# L_ftungssteuerung.net
KiCad netlist of a schematic drawn in EAGLE
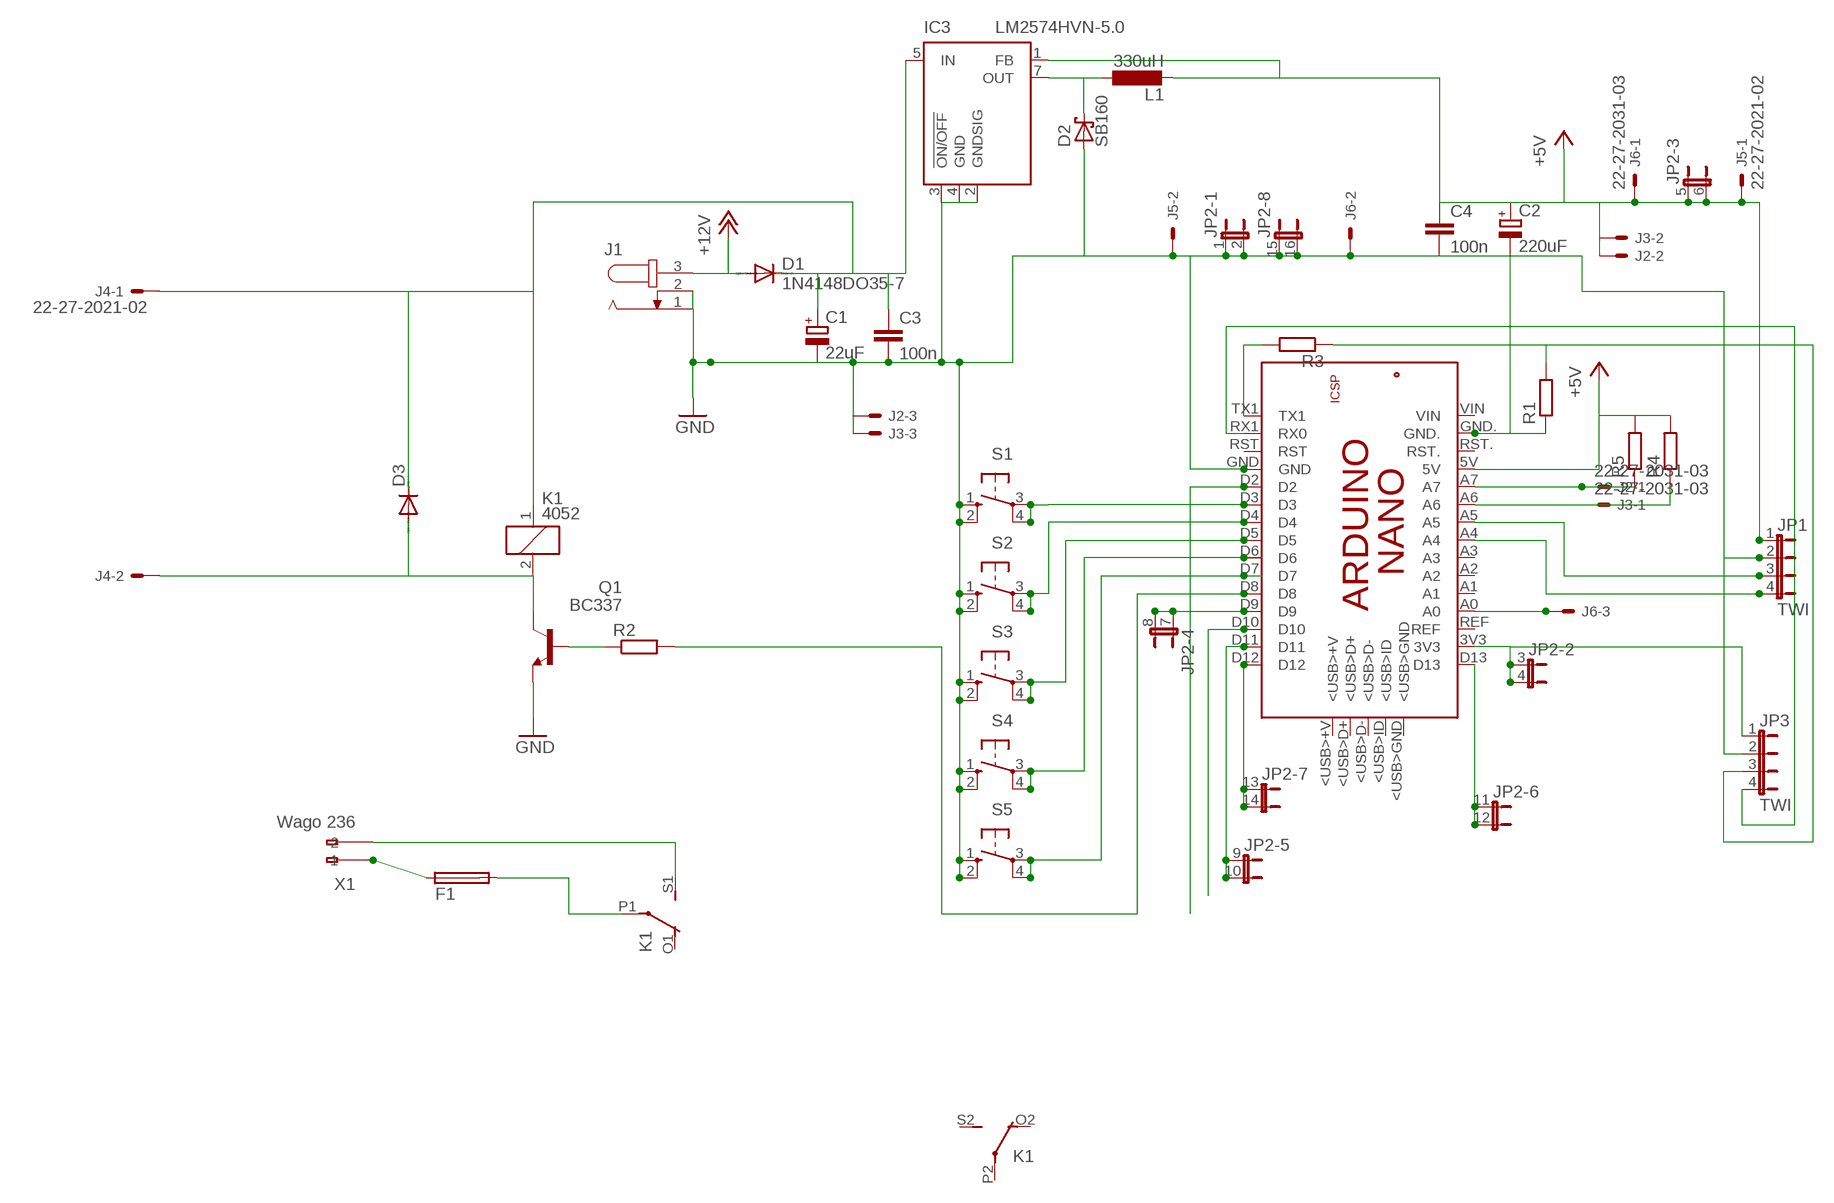
[diagram p0: schematic, sheet 1]

(export (version "E")
  (design (tool "Eeschema 10.0.6"))
  (components
    (comp (ref "C1")
      (value "22uF")
      (footprint "eagle-import:E2-5")
      (libsource (lib "eagle-import") (part "CPOL-EUE2-5"))
    )
    (comp (ref "C2")
      (value "220uF")
      (footprint "eagle-import:E5-10,5")
      (libsource (lib "eagle-import") (part "CPOL-EUE5-10.5"))
    )
    (comp (ref "C3")
      (value "100n")
      (footprint "eagle-import:C1206")
      (libsource (lib "eagle-import") (part "C-EUC1206"))
    )
    (comp (ref "C4")
      (value "100n")
      (footprint "eagle-import:C1206")
      (libsource (lib "eagle-import") (part "C-EUC1206"))
    )
    (comp (ref "D1")
      (value "1N4148DO35-7")
      (footprint "eagle-import:DO35-7")
      (libsource (lib "eagle-import") (part "1N4148DO35-7"))
    )
    (comp (ref "D2")
      (value "SB160")
      (footprint "eagle-import:DO41-7.6")
      (libsource (lib "eagle-import") (part "1N5817-B"))
    )
    (comp (ref "D3")
      (value "DIODE-DO41-7.6")
      (footprint "eagle-import:DO41-7.6")
      (libsource (lib "eagle-import") (part "DIODE-DO41-7.6"))
    )
    (comp (ref "F1")
      (value "SH22,5")
      (footprint "eagle-import:SH22,5")
      (fields (field (name "MF") "SCHURTER") (field (name "MPN") "0031.8201"))
      (libsource (lib "eagle-import") (part "SH22,5"))
    )
    (comp (ref "IC3")
      (value "LM2574HVN-5.0")
      (footprint "eagle-import:DIL08")
      (libsource (lib "eagle-import") (part "LM2574?-HVN5.0"))
    )
    (comp (ref "J1")
      (value "JACK-PLUG0")
      (footprint "eagle-import:SPC4077")
      (libsource (lib "eagle-import") (part "JACK-PLUG0"))
    )
    (comp (ref "J2")
      (value "22-27-2031-03")
      (footprint "eagle-import:6410-03")
      (libsource (lib "eagle-import") (part "22-?-0327-2031"))
    )
    (comp (ref "J3")
      (value "22-27-2031-03")
      (footprint "eagle-import:6410-03")
      (libsource (lib "eagle-import") (part "22-?-0327-2031"))
    )
    (comp (ref "J4")
      (value "22-27-2021-02")
      (footprint "eagle-import:6410-02")
      (libsource (lib "eagle-import") (part "22-?-0227-2021"))
    )
    (comp (ref "J5")
      (value "22-27-2021-02")
      (footprint "eagle-import:6410-02")
      (libsource (lib "eagle-import") (part "22-?-0227-2021"))
    )
    (comp (ref "J6")
      (value "22-27-2031-03")
      (footprint "eagle-import:6410-03")
      (libsource (lib "eagle-import") (part "22-?-0327-2031"))
    )
    (comp (ref "JP1")
      (value "TWI")
      (footprint "eagle-import:JP4")
      (libsource (lib "eagle-import") (part "JP4E"))
    )
    (comp (ref "JP2")
      (value "JP8QE")
      (footprint "eagle-import:JP8Q")
      (libsource (lib "eagle-import") (part "JP8QE"))
    )
    (comp (ref "JP3")
      (value "TWI")
      (footprint "eagle-import:JP4")
      (libsource (lib "eagle-import") (part "JP4E"))
    )
    (comp (ref "K1")
      (value "4052")
      (footprint "eagle-import:F4052")
      (libsource (lib "eagle-import") (part "4052"))
    )
    (comp (ref "L1")
      (value "330uH")
      (footprint "eagle-import:PIS47XX")
      (libsource (lib "eagle-import") (part "L-EUPIS47XX"))
    )
    (comp (ref "PCB1")
      (value "ARDUINO_NANO")
      (footprint "eagle-import:ARDUINO_NANO")
      (libsource (lib "eagle-import") (part "ARDUINO_NANO"))
    )
    (comp (ref "Q1")
      (value "BC337")
      (footprint "eagle-import:TO92")
      (libsource (lib "eagle-import") (part "BC337"))
    )
    (comp (ref "R1")
      (value "R-EU_R1206")
      (footprint "eagle-import:R1206")
      (libsource (lib "eagle-import") (part "R-EU_R1206"))
    )
    (comp (ref "R2")
      (value "R-EU_R1206")
      (footprint "eagle-import:R1206")
      (libsource (lib "eagle-import") (part "R-EU_R1206"))
    )
    (comp (ref "R3")
      (value "R-EU_R1206")
      (footprint "eagle-import:R1206")
      (libsource (lib "eagle-import") (part "R-EU_R1206"))
    )
    (comp (ref "R4")
      (value "R-EU_R1206")
      (footprint "eagle-import:R1206")
      (libsource (lib "eagle-import") (part "R-EU_R1206"))
    )
    (comp (ref "R5")
      (value "R-EU_R1206")
      (footprint "eagle-import:R1206")
      (libsource (lib "eagle-import") (part "R-EU_R1206"))
    )
    (comp (ref "S1")
      (value "10-XX")
      (footprint "eagle-import:B3F-10XX")
      (fields (field (name "MPN") "B3F-1000"))
      (libsource (lib "eagle-import") (part "10-XX"))
    )
    (comp (ref "S2")
      (value "10-XX")
      (footprint "eagle-import:B3F-10XX")
      (fields (field (name "MPN") "B3F-1000"))
      (libsource (lib "eagle-import") (part "10-XX"))
    )
    (comp (ref "S3")
      (value "10-XX")
      (footprint "eagle-import:B3F-10XX")
      (fields (field (name "MPN") "B3F-1000"))
      (libsource (lib "eagle-import") (part "10-XX"))
    )
    (comp (ref "S4")
      (value "10-XX")
      (footprint "eagle-import:B3F-10XX")
      (fields (field (name "MPN") "B3F-1000"))
      (libsource (lib "eagle-import") (part "10-XX"))
    )
    (comp (ref "S5")
      (value "10-XX")
      (footprint "eagle-import:B3F-10XX")
      (fields (field (name "MPN") "B3F-1000"))
      (libsource (lib "eagle-import") (part "10-XX"))
    )
    (comp (ref "X1")
      (value "Wago 236")
      (footprint "eagle-import:255-402-508")
      (libsource (lib "eagle-import") (part "255-402-508"))
    )
  )
  (nets
    (net (code "1") (name "+5V") (class "Default")
      (node (ref "C2") (pin "+") (pinfunction "+_+") (pintype "passive"))
      (node (ref "C4") (pin "1") (pinfunction "1_1") (pintype "passive"))
      (node (ref "IC3") (pin "1") (pinfunction "FB_1") (pintype "input"))
      (node (ref "J2") (pin "2") (pinfunction "S_2") (pintype "passive"))
      (node (ref "J3") (pin "2") (pinfunction "S_2") (pintype "passive"))
      (node (ref "J5") (pin "1") (pinfunction "S_1") (pintype "passive"))
      (node (ref "J6") (pin "1") (pinfunction "S_1") (pintype "passive"))
      (node (ref "JP1") (pin "1") (pinfunction "1_1") (pintype "passive"))
      (node (ref "JP2") (pin "5") (pinfunction "1_5") (pintype "passive"))
      (node (ref "JP2") (pin "6") (pinfunction "2_6") (pintype "passive"))
      (node (ref "L1") (pin "1") (pinfunction "2_1") (pintype "passive"))
      (node (ref "PCB1") (pin "5V") (pinfunction "5V_5V") (pintype "bidirectional"))
      (node (ref "R4") (pin "2") (pinfunction "2_2") (pintype "passive"))
      (node (ref "R5") (pin "2") (pinfunction "2_2") (pintype "passive"))
    )
    (net (code "2") (name "+12V") (class "Default")
      (node (ref "D1") (pin "A") (pinfunction "A_A") (pintype "passive"))
      (node (ref "J1") (pin "3") (pinfunction "3_3") (pintype "passive"))
    )
    (net (code "3") (name "GND") (class "Default")
      (node (ref "C1") (pin "-") (pinfunction "-_-") (pintype "passive"))
      (node (ref "C2") (pin "-") (pinfunction "-_-") (pintype "passive"))
      (node (ref "C3") (pin "2") (pinfunction "2_2") (pintype "passive"))
      (node (ref "C4") (pin "2") (pinfunction "2_2") (pintype "passive"))
      (node (ref "D2") (pin "A") (pinfunction "A_A") (pintype "passive"))
      (node (ref "IC3") (pin "2") (pinfunction "GNDSIG_2") (pintype "input"))
      (node (ref "IC3") (pin "3") (pinfunction "~{ON/OFF}_3") (pintype "input"))
      (node (ref "IC3") (pin "4") (pinfunction "GND_4") (pintype "power_in"))
      (node (ref "J1") (pin "1") (pinfunction "1_1") (pintype "passive"))
      (node (ref "J1") (pin "2") (pinfunction "2_2") (pintype "passive"))
      (node (ref "J2") (pin "3") (pinfunction "S_3") (pintype "passive"))
      (node (ref "J3") (pin "3") (pinfunction "S_3") (pintype "passive"))
      (node (ref "J5") (pin "2") (pinfunction "S_2") (pintype "passive"))
      (node (ref "J6") (pin "2") (pinfunction "S_2") (pintype "passive"))
      (node (ref "JP1") (pin "2") (pinfunction "2_2") (pintype "passive"))
      (node (ref "JP2") (pin "1") (pinfunction "1_1") (pintype "passive"))
      (node (ref "JP2") (pin "15") (pinfunction "1_15") (pintype "passive"))
      (node (ref "JP2") (pin "16") (pinfunction "2_16") (pintype "passive"))
      (node (ref "JP2") (pin "2") (pinfunction "2_2") (pintype "passive"))
      (node (ref "JP3") (pin "2") (pinfunction "2_2") (pintype "passive"))
      (node (ref "PCB1") (pin "GND") (pinfunction "GND_GND") (pintype "bidirectional"))
      (node (ref "PCB1") (pin "GND.") (pinfunction "GND._GND.") (pintype "bidirectional"))
      (node (ref "Q1") (pin "1") (pinfunction "E_1") (pintype "passive"))
      (node (ref "R1") (pin "1") (pinfunction "1_1") (pintype "passive"))
      (node (ref "S1") (pin "1") (pinfunction "S_1") (pintype "passive"))
      (node (ref "S1") (pin "2") (pinfunction "S1_2") (pintype "passive"))
      (node (ref "S2") (pin "1") (pinfunction "S_1") (pintype "passive"))
      (node (ref "S2") (pin "2") (pinfunction "S1_2") (pintype "passive"))
      (node (ref "S3") (pin "1") (pinfunction "S_1") (pintype "passive"))
      (node (ref "S3") (pin "2") (pinfunction "S1_2") (pintype "passive"))
      (node (ref "S4") (pin "1") (pinfunction "S_1") (pintype "passive"))
      (node (ref "S4") (pin "2") (pinfunction "S1_2") (pintype "passive"))
      (node (ref "S5") (pin "1") (pinfunction "S_1") (pintype "passive"))
      (node (ref "S5") (pin "2") (pinfunction "S1_2") (pintype "passive"))
    )
    (net (code "4") (name "Net-(IC3-IN)") (class "Default")
      (node (ref "C1") (pin "+") (pinfunction "+_+") (pintype "passive"))
      (node (ref "C3") (pin "1") (pinfunction "1_1") (pintype "passive"))
      (node (ref "D1") (pin "C") (pinfunction "C_C") (pintype "passive"))
      (node (ref "D3") (pin "C") (pinfunction "C_C") (pintype "passive"))
      (node (ref "IC3") (pin "5") (pinfunction "IN_5") (pintype "input"))
      (node (ref "J4") (pin "1") (pinfunction "S_1") (pintype "passive"))
      (node (ref "K1") (pin "1") (pinfunction "1_1") (pintype "passive"))
    )
    (net (code "5") (name "Net-(IC3-OUT)") (class "Default")
      (node (ref "D2") (pin "C") (pinfunction "C_C") (pintype "passive"))
      (node (ref "IC3") (pin "7") (pinfunction "OUT_7") (pintype "passive"))
      (node (ref "L1") (pin "2") (pinfunction "1_2") (pintype "passive"))
    )
    (net (code "6") (name "Net-(J2A-S)") (class "Default")
      (node (ref "J2") (pin "1") (pinfunction "S_1") (pintype "passive"))
      (node (ref "PCB1") (pin "A7") (pinfunction "A7_A7") (pintype "bidirectional"))
      (node (ref "R5") (pin "1") (pinfunction "1_1") (pintype "passive"))
    )
    (net (code "7") (name "Net-(J3A-S)") (class "Default")
      (node (ref "J3") (pin "1") (pinfunction "S_1") (pintype "passive"))
      (node (ref "PCB1") (pin "A6") (pinfunction "A6_A6") (pintype "bidirectional"))
      (node (ref "R4") (pin "1") (pinfunction "1_1") (pintype "passive"))
    )
    (net (code "8") (name "Net-(J4B-S)") (class "Default")
      (node (ref "D3") (pin "A") (pinfunction "A_A") (pintype "passive"))
      (node (ref "J4") (pin "2") (pinfunction "S_2") (pintype "passive"))
      (node (ref "K1") (pin "2") (pinfunction "2_2") (pintype "passive"))
      (node (ref "Q1") (pin "3") (pinfunction "C_3") (pintype "passive"))
    )
    (net (code "9") (name "Net-(J6C-S)") (class "Default")
      (node (ref "J6") (pin "3") (pinfunction "S_3") (pintype "passive"))
      (node (ref "PCB1") (pin "A0") (pinfunction "A0_A0") (pintype "bidirectional"))
    )
    (net (code "10") (name "Net-(JP1-Pad3)") (class "Default")
      (node (ref "JP1") (pin "3") (pinfunction "3_3") (pintype "passive"))
      (node (ref "PCB1") (pin "A5") (pinfunction "A5_A5") (pintype "bidirectional"))
    )
    (net (code "11") (name "Net-(JP1-Pad4)") (class "Default")
      (node (ref "JP1") (pin "4") (pinfunction "4_4") (pintype "passive"))
      (node (ref "PCB1") (pin "A4") (pinfunction "A4_A4") (pintype "bidirectional"))
    )
    (net (code "12") (name "Net-(JP2B-1)") (class "Default")
      (node (ref "JP2") (pin "3") (pinfunction "1_3") (pintype "passive"))
      (node (ref "JP2") (pin "4") (pinfunction "2_4") (pintype "passive"))
      (node (ref "JP3") (pin "1") (pinfunction "1_1") (pintype "passive"))
      (node (ref "PCB1") (pin "3V3") (pinfunction "3V3_3V3") (pintype "bidirectional"))
    )
    (net (code "13") (name "Net-(JP2D-1)") (class "Default")
      (node (ref "JP2") (pin "7") (pinfunction "1_7") (pintype "passive"))
      (node (ref "JP2") (pin "8") (pinfunction "2_8") (pintype "passive"))
      (node (ref "PCB1") (pin "D9") (pinfunction "D9_D9") (pintype "bidirectional"))
    )
    (net (code "14") (name "Net-(JP2E-1)") (class "Default")
      (node (ref "JP2") (pin "10") (pinfunction "2_10") (pintype "passive"))
      (node (ref "JP2") (pin "9") (pinfunction "1_9") (pintype "passive"))
      (node (ref "PCB1") (pin "D11") (pinfunction "D11_D11") (pintype "bidirectional"))
    )
    (net (code "15") (name "Net-(JP2F-1)") (class "Default")
      (node (ref "JP2") (pin "11") (pinfunction "1_11") (pintype "passive"))
      (node (ref "JP2") (pin "12") (pinfunction "2_12") (pintype "passive"))
      (node (ref "PCB1") (pin "D13") (pinfunction "D13_D13") (pintype "bidirectional"))
    )
    (net (code "16") (name "Net-(JP2G-1)") (class "Default")
      (node (ref "JP2") (pin "13") (pinfunction "1_13") (pintype "passive"))
      (node (ref "JP2") (pin "14") (pinfunction "2_14") (pintype "passive"))
      (node (ref "PCB1") (pin "D12") (pinfunction "D12_D12") (pintype "bidirectional"))
    )
    (net (code "17") (name "Net-(JP3-Pad3)") (class "Default")
      (node (ref "JP3") (pin "3") (pinfunction "3_3") (pintype "passive"))
      (node (ref "R1") (pin "2") (pinfunction "2_2") (pintype "passive"))
      (node (ref "R3") (pin "1") (pinfunction "1_1") (pintype "passive"))
    )
    (net (code "18") (name "Net-(K1B-P)") (class "Default")
      (node (ref "F1") (pin "2") (pinfunction "2_2") (pintype "passive"))
      (node (ref "K1") (pin "P1") (pinfunction "P_P1") (pintype "passive"))
    )
    (net (code "19") (name "Net-(K1B-S)") (class "Default")
      (node (ref "K1") (pin "S1") (pinfunction "S_S1") (pintype "passive"))
      (node (ref "X1") (pin "A2") (pinfunction "-2_A2") (pintype "passive"))
    )
    (net (code "20") (name "Net-(PCB1-PadD8)") (class "Default")
      (node (ref "PCB1") (pin "D8") (pinfunction "D8_D8") (pintype "bidirectional"))
      (node (ref "R2") (pin "2") (pinfunction "2_2") (pintype "passive"))
    )
    (net (code "21") (name "Net-(PCB1-PadTX1)") (class "Default")
      (node (ref "PCB1") (pin "TX1") (pinfunction "TX1_TX1") (pintype "bidirectional"))
      (node (ref "R3") (pin "2") (pinfunction "2_2") (pintype "passive"))
    )
    (net (code "22") (name "Net-(PCB1-RX0)") (class "Default")
      (node (ref "JP3") (pin "4") (pinfunction "4_4") (pintype "passive"))
      (node (ref "PCB1") (pin "RX1") (pinfunction "RX0_RX1") (pintype "bidirectional"))
    )
    (net (code "23") (name "Net-(Q1-B)") (class "Default")
      (node (ref "Q1") (pin "2") (pinfunction "B_2") (pintype "passive"))
      (node (ref "R2") (pin "1") (pinfunction "1_1") (pintype "passive"))
    )
    (net (code "24") (name "Net-(S1-P)") (class "Default")
      (node (ref "PCB1") (pin "D3") (pinfunction "D3_D3") (pintype "bidirectional"))
      (node (ref "S1") (pin "3") (pinfunction "P_3") (pintype "passive"))
      (node (ref "S1") (pin "4") (pinfunction "P1_4") (pintype "passive"))
    )
    (net (code "25") (name "Net-(S2-P)") (class "Default")
      (node (ref "PCB1") (pin "D4") (pinfunction "D4_D4") (pintype "bidirectional"))
      (node (ref "S2") (pin "3") (pinfunction "P_3") (pintype "passive"))
      (node (ref "S2") (pin "4") (pinfunction "P1_4") (pintype "passive"))
    )
    (net (code "26") (name "Net-(S3-P)") (class "Default")
      (node (ref "PCB1") (pin "D5") (pinfunction "D5_D5") (pintype "bidirectional"))
      (node (ref "S3") (pin "3") (pinfunction "P_3") (pintype "passive"))
      (node (ref "S3") (pin "4") (pinfunction "P1_4") (pintype "passive"))
    )
    (net (code "27") (name "Net-(S4-P)") (class "Default")
      (node (ref "PCB1") (pin "D6") (pinfunction "D6_D6") (pintype "bidirectional"))
      (node (ref "S4") (pin "3") (pinfunction "P_3") (pintype "passive"))
      (node (ref "S4") (pin "4") (pinfunction "P1_4") (pintype "passive"))
    )
    (net (code "28") (name "Net-(S5-P)") (class "Default")
      (node (ref "PCB1") (pin "D7") (pinfunction "D7_D7") (pintype "bidirectional"))
      (node (ref "S5") (pin "3") (pinfunction "P_3") (pintype "passive"))
      (node (ref "S5") (pin "4") (pinfunction "P1_4") (pintype "passive"))
    )
    (net (code "29") (name "Net-(X1--1)") (class "Default")
      (node (ref "F1") (pin "1") (pinfunction "1_1") (pintype "passive"))
      (node (ref "X1") (pin "A1") (pinfunction "-1_A1") (pintype "passive"))
    )
    (net (code "30") (name "unconnected-(K1B-O-PadO1)") (class "Default")
      (node (ref "K1") (pin "O1") (pinfunction "O_O1") (pintype "passive"))
    )
    (net (code "31") (name "unconnected-(K1C-O-PadO2)") (class "Default")
      (node (ref "K1") (pin "O2") (pinfunction "O_O2") (pintype "passive"))
    )
    (net (code "32") (name "unconnected-(K1C-P-PadP2)") (class "Default")
      (node (ref "K1") (pin "P2") (pinfunction "P_P2") (pintype "passive"))
    )
    (net (code "33") (name "unconnected-(K1C-S-PadS2)") (class "Default")
      (node (ref "K1") (pin "S2") (pinfunction "S_S2") (pintype "passive"))
    )
    (net (code "34") (name "unconnected-(PCB1-Pad5V.)") (class "Default")
      (node (ref "PCB1") (pin "5V.") (pinfunction "5V._5V.") (pintype "bidirectional"))
    )
    (net (code "35") (name "unconnected-(PCB1-Pad<USB>+V)") (class "Default")
      (node (ref "PCB1") (pin "<USB>+V") (pinfunction "<USB>+V_<USB>+V") (pintype "bidirectional"))
    )
    (net (code "36") (name "unconnected-(PCB1-Pad<USB>D+)") (class "Default")
      (node (ref "PCB1") (pin "<USB>D+") (pinfunction "<USB>D+_<USB>D+") (pintype "bidirectional"))
    )
    (net (code "37") (name "unconnected-(PCB1-Pad<USB>D-)") (class "Default")
      (node (ref "PCB1") (pin "<USB>D-") (pinfunction "<USB>D-_<USB>D-") (pintype "bidirectional"))
    )
    (net (code "38") (name "unconnected-(PCB1-Pad<USB>GND)") (class "Default")
      (node (ref "PCB1") (pin "<USB>GND") (pinfunction "<USB>GND_<USB>GND") (pintype "bidirectional"))
    )
    (net (code "39") (name "unconnected-(PCB1-Pad<USB>ID)") (class "Default")
      (node (ref "PCB1") (pin "<USB>ID") (pinfunction "<USB>ID_<USB>ID") (pintype "bidirectional"))
    )
    (net (code "40") (name "unconnected-(PCB1-PadA1)") (class "Default")
      (node (ref "PCB1") (pin "A1") (pinfunction "A1_A1") (pintype "bidirectional"))
    )
    (net (code "41") (name "unconnected-(PCB1-PadA2)") (class "Default")
      (node (ref "PCB1") (pin "A2") (pinfunction "A2_A2") (pintype "bidirectional"))
    )
    (net (code "42") (name "unconnected-(PCB1-PadA3)") (class "Default")
      (node (ref "PCB1") (pin "A3") (pinfunction "A3_A3") (pintype "bidirectional"))
    )
    (net (code "43") (name "unconnected-(PCB1-PadD2)") (class "Default")
      (node (ref "PCB1") (pin "D2") (pinfunction "D2_D2") (pintype "bidirectional"))
    )
    (net (code "44") (name "unconnected-(PCB1-PadD10)") (class "Default")
      (node (ref "PCB1") (pin "D10") (pinfunction "D10_D10") (pintype "bidirectional"))
    )
    (net (code "45") (name "unconnected-(PCB1-PadGND_)") (class "Default")
      (node (ref "PCB1") (pin "GND_") (pinfunction "GND__GND_") (pintype "bidirectional"))
    )
    (net (code "46") (name "unconnected-(PCB1-PadMISO)") (class "Default")
      (node (ref "PCB1") (pin "MISO") (pinfunction "MISO_MISO") (pintype "bidirectional"))
    )
    (net (code "47") (name "unconnected-(PCB1-PadMOSI)") (class "Default")
      (node (ref "PCB1") (pin "MOSI") (pinfunction "MOSI_MOSI") (pintype "bidirectional"))
    )
    (net (code "48") (name "unconnected-(PCB1-PadREF)") (class "Default")
      (node (ref "PCB1") (pin "REF") (pinfunction "REF_REF") (pintype "bidirectional"))
    )
    (net (code "49") (name "unconnected-(PCB1-PadRESET..)") (class "Default")
      (node (ref "PCB1") (pin "RESET..") (pinfunction "RESET.._RESET..") (pintype "bidirectional"))
    )
    (net (code "50") (name "unconnected-(PCB1-PadRST)") (class "Default")
      (node (ref "PCB1") (pin "RST") (pinfunction "RST_RST") (pintype "bidirectional"))
    )
    (net (code "51") (name "unconnected-(PCB1-PadRST.)") (class "Default")
      (node (ref "PCB1") (pin "RST.") (pinfunction "RST._RST.") (pintype "bidirectional"))
    )
    (net (code "52") (name "unconnected-(PCB1-PadSCK)") (class "Default")
      (node (ref "PCB1") (pin "SCK") (pinfunction "SCK_SCK") (pintype "bidirectional"))
    )
    (net (code "53") (name "unconnected-(PCB1-PadVIN)") (class "Default")
      (node (ref "PCB1") (pin "VIN") (pinfunction "VIN_VIN") (pintype "bidirectional"))
    )
    (net (code "54") (name "unconnected-(X1-B-1-PadB1)") (class "Default")
      (node (ref "X1") (pin "B1") (pinfunction "B-1_B1") (pintype "passive"))
    )
    (net (code "55") (name "unconnected-(X1-B-2-PadB2)") (class "Default")
      (node (ref "X1") (pin "B2") (pinfunction "B-2_B2") (pintype "passive"))
    )
  )
)
